# niveau.net
KiCad netlist of a schematic drawn in EAGLE
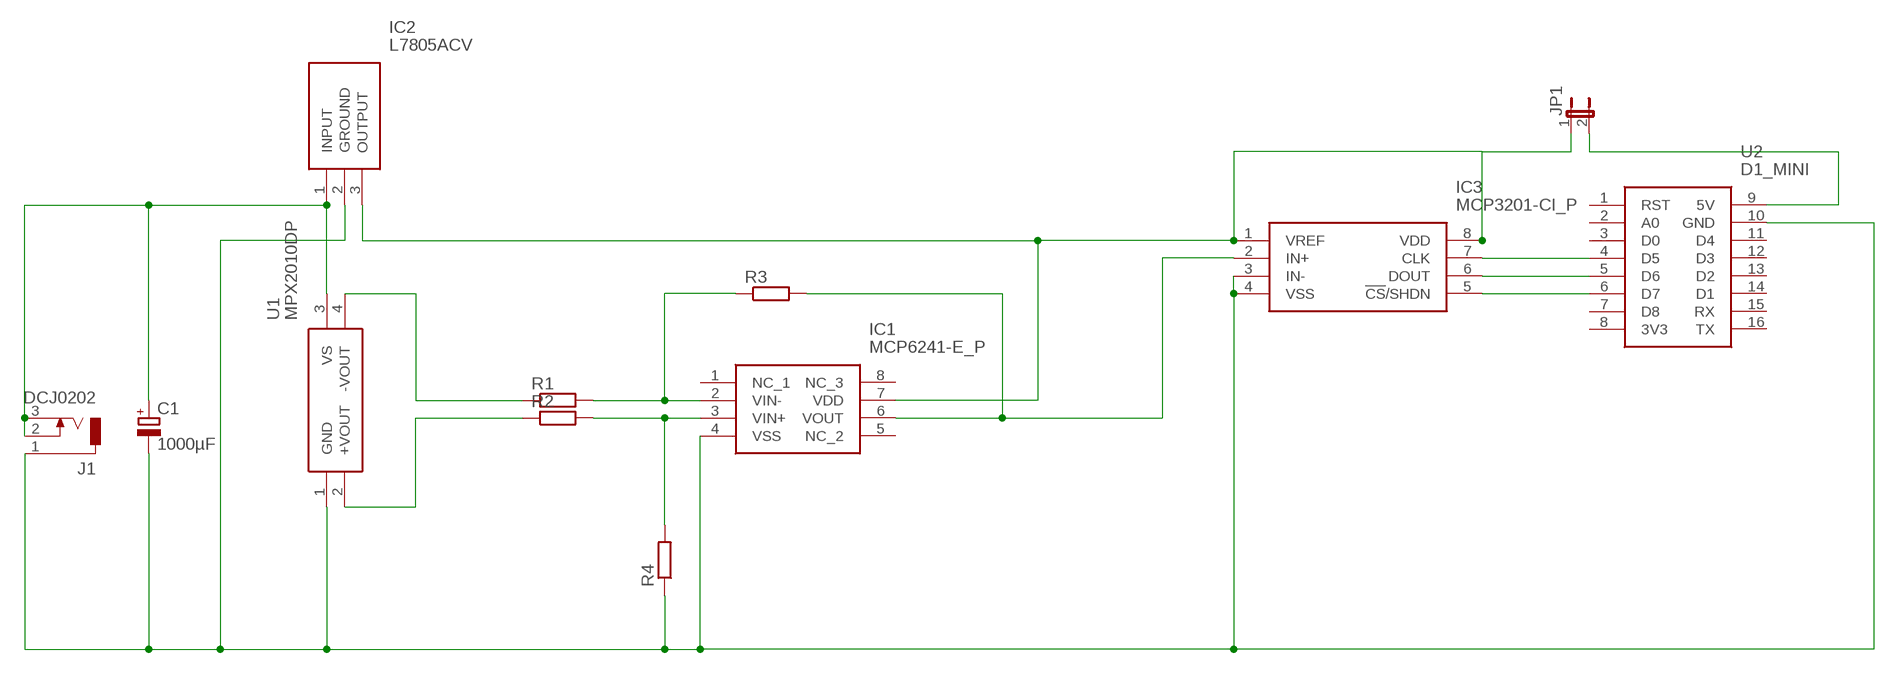
[diagram p0: schematic, sheet 1]

(export (version "E")
  (design (tool "Eeschema 10.0.6"))
  (components
    (comp (ref "C1")
      (value "1000µF")
      (footprint "eagle-import:EB35D")
      (libsource (lib "eagle-import") (part "CPOL-EUE10-35"))
    )
    (comp (ref "IC1")
      (value "MCP6241-E_P")
      (footprint "eagle-import:DIP781W56P254L950H533Q8N")
      (fields (field (name "ARROW_PART_NUMBER") "MCP6241-E/P") (field (name "RS_PART_NUMBER") "0403018"))
      (libsource (lib "eagle-import") (part "MCP6241-E_P"))
    )
    (comp (ref "IC2")
      (value "L7805ACV")
      (footprint "eagle-import:TO270P460X1020X2008-3P")
      (fields (field (name "RS_PART_NUMBER") "1686059"))
      (libsource (lib "eagle-import") (part "L7805ACV"))
    )
    (comp (ref "IC3")
      (value "MCP3201-CI_P")
      (footprint "eagle-import:DIP781W56P254L950H533Q8N")
      (fields (field (name "ARROW_PART_NUMBER") "MCP3201-CI/P") (field (name "RS_PART_NUMBER") "8895770"))
      (libsource (lib "eagle-import") (part "MCP3201-CI_P"))
    )
    (comp (ref "J1")
      (value "DCJ0202")
      (footprint "eagle-import:DCJ0202")
      (libsource (lib "eagle-import") (part "DCJ0202"))
    )
    (comp (ref "JP1")
      (value "JP1E")
      (footprint "eagle-import:JP1")
      (libsource (lib "eagle-import") (part "JP1E"))
    )
    (comp (ref "R1")
      (value "R-EU_0309/10")
      (footprint "eagle-import:0309_10")
      (libsource (lib "eagle-import") (part "R-EU_0309/10"))
    )
    (comp (ref "R2")
      (value "R-EU_0309/10")
      (footprint "eagle-import:0309_10")
      (libsource (lib "eagle-import") (part "R-EU_0309/10"))
    )
    (comp (ref "R3")
      (value "R-EU_0309/10")
      (footprint "eagle-import:0309_10")
      (libsource (lib "eagle-import") (part "R-EU_0309/10"))
    )
    (comp (ref "R4")
      (value "R-EU_0309/10")
      (footprint "eagle-import:0309_10")
      (libsource (lib "eagle-import") (part "R-EU_0309/10"))
    )
    (comp (ref "U1")
      (value "MPX2010DP")
      (footprint "eagle-import:CASE-344C-01-ISSUE-B")
      (fields (field (name "RS_PART_NUMBER") "7191021"))
      (libsource (lib "eagle-import") (part "MPX2010DP"))
    )
    (comp (ref "U2")
      (value "D1_MINI")
      (footprint "eagle-import:D1-MINI")
      (fields (field (name "ARROW_PART_NUMBER") "D1 Mini"))
      (libsource (lib "eagle-import") (part "D1_MINI"))
    )
  )
  (nets
    (net (code "1") (name "Net-(IC1-VDD)") (class "Default")
      (node (ref "IC1") (pin "7") (pinfunction "VDD_7") (pintype "bidirectional"))
      (node (ref "IC2") (pin "3") (pinfunction "OUTPUT_3") (pintype "output"))
      (node (ref "IC3") (pin "1") (pinfunction "VREF_1") (pintype "bidirectional"))
      (node (ref "IC3") (pin "8") (pinfunction "VDD_8") (pintype "bidirectional"))
      (node (ref "JP1") (pin "1") (pinfunction "1_1") (pintype "passive"))
    )
    (net (code "2") (name "Net-(IC1-VIN+)") (class "Default")
      (node (ref "IC1") (pin "3") (pinfunction "VIN+_3") (pintype "bidirectional"))
      (node (ref "R2") (pin "2") (pinfunction "2_2") (pintype "passive"))
      (node (ref "R4") (pin "2") (pinfunction "2_2") (pintype "passive"))
    )
    (net (code "3") (name "Net-(IC1-VIN-)") (class "Default")
      (node (ref "IC1") (pin "2") (pinfunction "VIN-_2") (pintype "bidirectional"))
      (node (ref "R1") (pin "2") (pinfunction "2_2") (pintype "passive"))
      (node (ref "R3") (pin "1") (pinfunction "1_1") (pintype "passive"))
    )
    (net (code "4") (name "Net-(IC1-VOUT)") (class "Default")
      (node (ref "IC1") (pin "6") (pinfunction "VOUT_6") (pintype "bidirectional"))
      (node (ref "IC3") (pin "2") (pinfunction "IN+_2") (pintype "bidirectional"))
      (node (ref "R3") (pin "2") (pinfunction "2_2") (pintype "passive"))
    )
    (net (code "5") (name "Net-(IC1-VSS)") (class "Default")
      (node (ref "C1") (pin "-") (pinfunction "-_-") (pintype "passive"))
      (node (ref "IC1") (pin "4") (pinfunction "VSS_4") (pintype "bidirectional"))
      (node (ref "IC2") (pin "2") (pinfunction "GROUND_2") (pintype "power_in"))
      (node (ref "IC3") (pin "3") (pinfunction "IN-_3") (pintype "bidirectional"))
      (node (ref "IC3") (pin "4") (pinfunction "VSS_4") (pintype "bidirectional"))
      (node (ref "J1") (pin "1") (pinfunction "1_1") (pintype "passive"))
      (node (ref "R4") (pin "1") (pinfunction "1_1") (pintype "passive"))
      (node (ref "U1") (pin "1") (pinfunction "GND_1") (pintype "bidirectional"))
      (node (ref "U2") (pin "10") (pinfunction "GND_10") (pintype "bidirectional"))
    )
    (net (code "6") (name "Net-(IC2-INPUT)") (class "Default")
      (node (ref "C1") (pin "+") (pinfunction "+_+") (pintype "passive"))
      (node (ref "IC2") (pin "1") (pinfunction "INPUT_1") (pintype "input"))
      (node (ref "J1") (pin "2") (pinfunction "2_2") (pintype "passive"))
      (node (ref "J1") (pin "3") (pinfunction "3_3") (pintype "passive"))
      (node (ref "U1") (pin "3") (pinfunction "VS_3") (pintype "bidirectional"))
    )
    (net (code "7") (name "Net-(IC3-CLK)") (class "Default")
      (node (ref "IC3") (pin "7") (pinfunction "CLK_7") (pintype "bidirectional"))
      (node (ref "U2") (pin "4") (pinfunction "D5_4") (pintype "bidirectional"))
    )
    (net (code "8") (name "Net-(IC3-DOUT)") (class "Default")
      (node (ref "IC3") (pin "6") (pinfunction "DOUT_6") (pintype "bidirectional"))
      (node (ref "U2") (pin "5") (pinfunction "D6_5") (pintype "bidirectional"))
    )
    (net (code "9") (name "Net-(IC3-~{CS}{slash}SHDN)") (class "Default")
      (node (ref "IC3") (pin "5") (pinfunction "~{CS}/SHDN_5") (pintype "bidirectional"))
      (node (ref "U2") (pin "6") (pinfunction "D7_6") (pintype "bidirectional"))
    )
    (net (code "10") (name "Net-(U1-+VOUT)") (class "Default")
      (node (ref "R2") (pin "1") (pinfunction "1_1") (pintype "passive"))
      (node (ref "U1") (pin "2") (pinfunction "+VOUT_2") (pintype "bidirectional"))
    )
    (net (code "11") (name "Net-(U1--VOUT)") (class "Default")
      (node (ref "R1") (pin "1") (pinfunction "1_1") (pintype "passive"))
      (node (ref "U1") (pin "4") (pinfunction "-VOUT_4") (pintype "bidirectional"))
    )
    (net (code "12") (name "Net-(U2-5V)") (class "Default")
      (node (ref "JP1") (pin "2") (pinfunction "2_2") (pintype "passive"))
      (node (ref "U2") (pin "9") (pinfunction "5V_9") (pintype "bidirectional"))
    )
    (net (code "13") (name "unconnected-(IC1-NC_1-Pad1)") (class "Default")
      (node (ref "IC1") (pin "1") (pinfunction "NC_1_1") (pintype "bidirectional"))
    )
    (net (code "14") (name "unconnected-(IC1-NC_2-Pad5)") (class "Default")
      (node (ref "IC1") (pin "5") (pinfunction "NC_2_5") (pintype "bidirectional"))
    )
    (net (code "15") (name "unconnected-(IC1-NC_3-Pad8)") (class "Default")
      (node (ref "IC1") (pin "8") (pinfunction "NC_3_8") (pintype "bidirectional"))
    )
    (net (code "16") (name "unconnected-(U2-3V3-Pad8)") (class "Default")
      (node (ref "U2") (pin "8") (pinfunction "3V3_8") (pintype "bidirectional"))
    )
    (net (code "17") (name "unconnected-(U2-A0-Pad2)") (class "Default")
      (node (ref "U2") (pin "2") (pinfunction "A0_2") (pintype "bidirectional"))
    )
    (net (code "18") (name "unconnected-(U2-D0-Pad3)") (class "Default")
      (node (ref "U2") (pin "3") (pinfunction "D0_3") (pintype "bidirectional"))
    )
    (net (code "19") (name "unconnected-(U2-D1-Pad14)") (class "Default")
      (node (ref "U2") (pin "14") (pinfunction "D1_14") (pintype "bidirectional"))
    )
    (net (code "20") (name "unconnected-(U2-D2-Pad13)") (class "Default")
      (node (ref "U2") (pin "13") (pinfunction "D2_13") (pintype "bidirectional"))
    )
    (net (code "21") (name "unconnected-(U2-D3-Pad12)") (class "Default")
      (node (ref "U2") (pin "12") (pinfunction "D3_12") (pintype "bidirectional"))
    )
    (net (code "22") (name "unconnected-(U2-D4-Pad11)") (class "Default")
      (node (ref "U2") (pin "11") (pinfunction "D4_11") (pintype "bidirectional"))
    )
    (net (code "23") (name "unconnected-(U2-D8-Pad7)") (class "Default")
      (node (ref "U2") (pin "7") (pinfunction "D8_7") (pintype "bidirectional"))
    )
    (net (code "24") (name "unconnected-(U2-RST-Pad1)") (class "Default")
      (node (ref "U2") (pin "1") (pinfunction "RST_1") (pintype "bidirectional"))
    )
    (net (code "25") (name "unconnected-(U2-RX-Pad15)") (class "Default")
      (node (ref "U2") (pin "15") (pinfunction "RX_15") (pintype "bidirectional"))
    )
    (net (code "26") (name "unconnected-(U2-TX-Pad16)") (class "Default")
      (node (ref "U2") (pin "16") (pinfunction "TX_16") (pintype "bidirectional"))
    )
  )
)
